# I2C_Keypad.net
KiCad netlist of a schematic drawn in Altium Designer
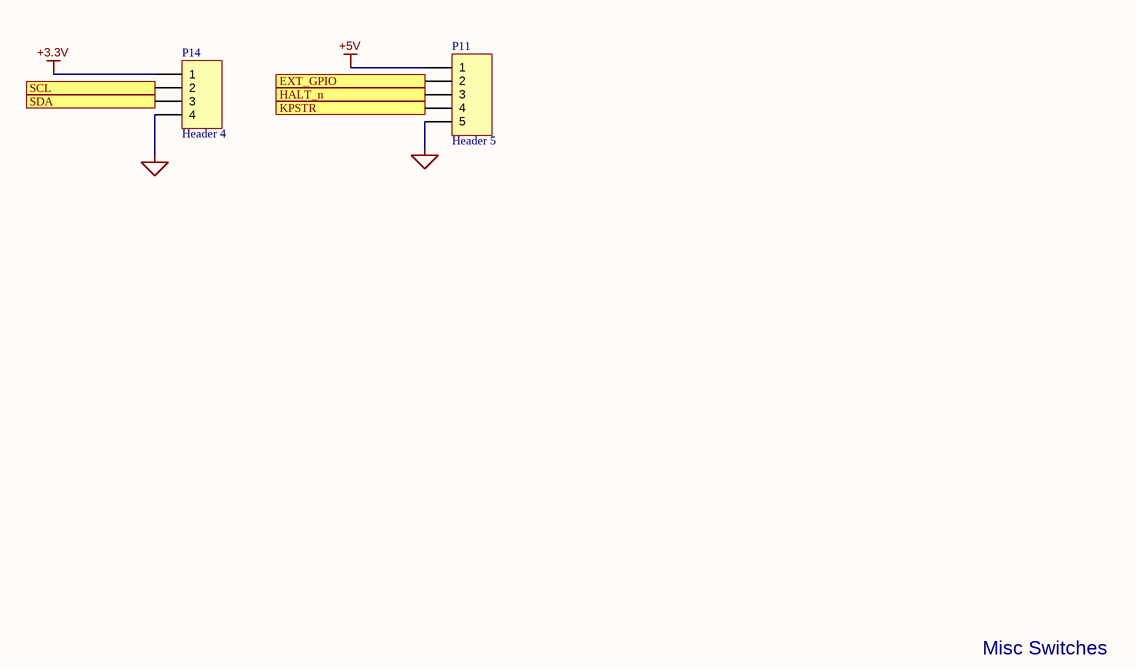
[diagram p0: I2C_Keypad.SchDoc]

(export (version "E")
  (design (tool "Eeschema 10.0.6"))
  (components
    (comp (ref "P11")
      (value "Header 5")
      (footprint "HDR1X5")
      (description "Header, 5-Pin")
      (fields (field (name "PUBLISHER") "Altium Limited"))
      (libsource (lib "PrintNC_GRBLHAL_Breakout") (part "Header 5"))
    )
    (comp (ref "P14")
      (value "Header 4")
      (footprint "HDR1X4")
      (description "Header, 4-Pin")
      (fields (field (name "PUBLISHER") "Altium Limited"))
      (libsource (lib "PrintNC_GRBLHAL_Breakout") (part "Header 4"))
    )
  )
  (nets
    (net (code "1") (name "+3.3V") (class "Default")
      (node (ref "P14") (pin "1") (pinfunction "1_1") (pintype "passive"))
    )
    (net (code "2") (name "+5V") (class "Default")
      (node (ref "P11") (pin "1") (pinfunction "1_1") (pintype "passive"))
    )
    (net (code "3") (name "/EXT_GPIO") (class "Default")
      (node (ref "P11") (pin "2") (pinfunction "2_2") (pintype "passive"))
    )
    (net (code "4") (name "/HALT_n") (class "Default")
      (node (ref "P11") (pin "3") (pinfunction "3_3") (pintype "passive"))
    )
    (net (code "5") (name "/KPSTR") (class "Default")
      (node (ref "P11") (pin "4") (pinfunction "4_4") (pintype "passive"))
    )
    (net (code "6") (name "/SCL") (class "Default")
      (node (ref "P14") (pin "2") (pinfunction "2_2") (pintype "passive"))
    )
    (net (code "7") (name "/SDA") (class "Default")
      (node (ref "P14") (pin "3") (pinfunction "3_3") (pintype "passive"))
    )
    (net (code "8") (name "MCU_GND") (class "Default")
      (node (ref "P11") (pin "5") (pinfunction "5_5") (pintype "passive"))
      (node (ref "P14") (pin "4") (pinfunction "4_4") (pintype "passive"))
    )
  )
)
